# w2aew.net
KiCad netlist of a schematic drawn in EAGLE
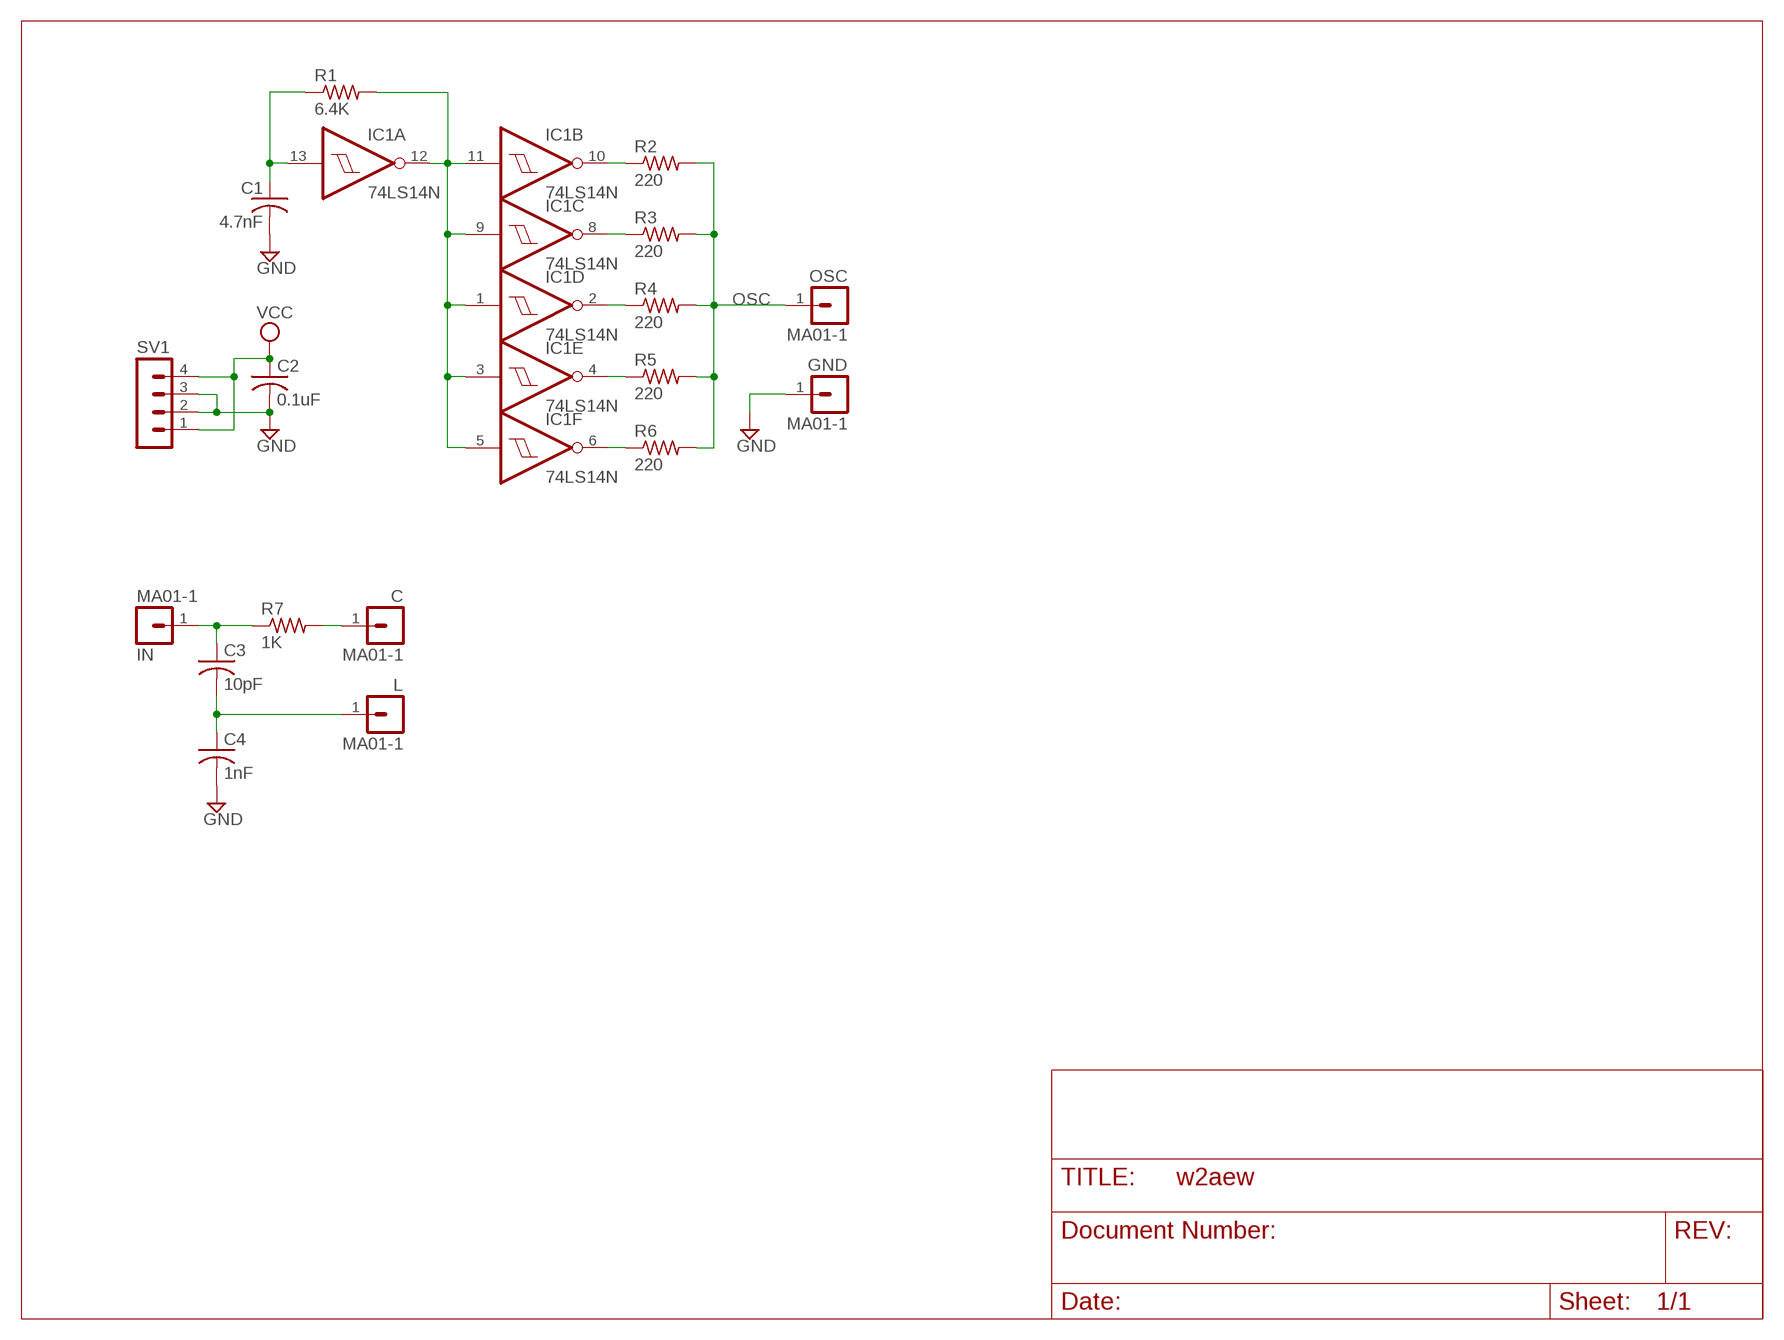
[diagram p0: schematic, sheet 1]

(export (version "E")
  (design (tool "Eeschema 10.0.6"))
  (components
    (comp (ref "C")
      (value "MA01-1")
      (footprint "eagle-import:MA01-1")
      (libsource (lib "eagle-import") (part "MA01-1"))
    )
    (comp (ref "C1")
      (value "4.7nF")
      (footprint "eagle-import:C050-025X075")
      (libsource (lib "eagle-import") (part "C-US050-025X075"))
    )
    (comp (ref "C2")
      (value "0.1uF")
      (footprint "eagle-import:C050-025X075")
      (libsource (lib "eagle-import") (part "C-US050-025X075"))
    )
    (comp (ref "C3")
      (value "10pF")
      (footprint "eagle-import:C050-025X075")
      (libsource (lib "eagle-import") (part "C-US050-025X075"))
    )
    (comp (ref "C4")
      (value "1nF")
      (footprint "eagle-import:C050-025X075")
      (libsource (lib "eagle-import") (part "C-US050-025X075"))
    )
    (comp (ref "GND")
      (value "MA01-1")
      (footprint "eagle-import:MA01-1")
      (libsource (lib "eagle-import") (part "MA01-1"))
    )
    (comp (ref "IC1")
      (value "74LS14N")
      (footprint "eagle-import:DIL14")
      (libsource (lib "eagle-import") (part "7414NLS"))
    )
    (comp (ref "IN")
      (value "MA01-1")
      (footprint "eagle-import:MA01-1")
      (libsource (lib "eagle-import") (part "MA01-1"))
    )
    (comp (ref "L")
      (value "MA01-1")
      (footprint "eagle-import:MA01-1")
      (libsource (lib "eagle-import") (part "MA01-1"))
    )
    (comp (ref "OSC")
      (value "MA01-1")
      (footprint "eagle-import:MA01-1")
      (libsource (lib "eagle-import") (part "MA01-1"))
    )
    (comp (ref "R1")
      (value "6.4K")
      (footprint "eagle-import:0207_10")
      (libsource (lib "eagle-import") (part "R-US_0207/10"))
    )
    (comp (ref "R2")
      (value "220")
      (footprint "eagle-import:0207_10")
      (libsource (lib "eagle-import") (part "R-US_0207/10"))
    )
    (comp (ref "R3")
      (value "220")
      (footprint "eagle-import:0207_10")
      (libsource (lib "eagle-import") (part "R-US_0207/10"))
    )
    (comp (ref "R4")
      (value "220")
      (footprint "eagle-import:0207_10")
      (libsource (lib "eagle-import") (part "R-US_0207/10"))
    )
    (comp (ref "R5")
      (value "220")
      (footprint "eagle-import:0207_10")
      (libsource (lib "eagle-import") (part "R-US_0207/10"))
    )
    (comp (ref "R6")
      (value "220")
      (footprint "eagle-import:0207_10")
      (libsource (lib "eagle-import") (part "R-US_0207/10"))
    )
    (comp (ref "R7")
      (value "1K")
      (footprint "eagle-import:0207_10")
      (libsource (lib "eagle-import") (part "R-US_0207/10"))
    )
    (comp (ref "SV1")
      (value "MA04-1")
      (footprint "eagle-import:MA04-1")
      (libsource (lib "eagle-import") (part "MA04-1"))
    )
  )
  (nets
    (net (code "1") (name "/OSC") (class "Default")
      (node (ref "OSC") (pin "1") (pinfunction "1_1") (pintype "passive"))
      (node (ref "R2") (pin "2") (pinfunction "2_2") (pintype "passive"))
      (node (ref "R3") (pin "2") (pinfunction "2_2") (pintype "passive"))
      (node (ref "R4") (pin "2") (pinfunction "2_2") (pintype "passive"))
      (node (ref "R5") (pin "2") (pinfunction "2_2") (pintype "passive"))
      (node (ref "R6") (pin "2") (pinfunction "2_2") (pintype "passive"))
    )
    (net (code "2") (name "GND") (class "Default")
      (node (ref "C1") (pin "2") (pinfunction "2_2") (pintype "passive"))
      (node (ref "C2") (pin "2") (pinfunction "2_2") (pintype "passive"))
      (node (ref "C4") (pin "2") (pinfunction "2_2") (pintype "passive"))
      (node (ref "GND") (pin "1") (pinfunction "1_1") (pintype "passive"))
      (node (ref "SV1") (pin "2") (pinfunction "2_2") (pintype "passive"))
      (node (ref "SV1") (pin "3") (pinfunction "3_3") (pintype "passive"))
    )
    (net (code "3") (name "Net-(C-Pad1)") (class "Default")
      (node (ref "C") (pin "1") (pinfunction "1_1") (pintype "passive"))
      (node (ref "R7") (pin "2") (pinfunction "2_2") (pintype "passive"))
    )
    (net (code "4") (name "Net-(C3-Pad1)") (class "Default")
      (node (ref "C3") (pin "1") (pinfunction "1_1") (pintype "passive"))
      (node (ref "IN") (pin "1") (pinfunction "1_1") (pintype "passive"))
      (node (ref "R7") (pin "1") (pinfunction "1_1") (pintype "passive"))
    )
    (net (code "5") (name "Net-(C3-Pad2)") (class "Default")
      (node (ref "C3") (pin "2") (pinfunction "2_2") (pintype "passive"))
      (node (ref "C4") (pin "1") (pinfunction "1_1") (pintype "passive"))
      (node (ref "L") (pin "1") (pinfunction "1_1") (pintype "passive"))
    )
    (net (code "6") (name "Net-(IC1A-I)") (class "Default")
      (node (ref "C1") (pin "1") (pinfunction "1_1") (pintype "passive"))
      (node (ref "IC1") (pin "13") (pinfunction "I_13") (pintype "input"))
      (node (ref "R1") (pin "1") (pinfunction "1_1") (pintype "passive"))
    )
    (net (code "7") (name "Net-(IC1A-O)") (class "Default")
      (node (ref "IC1") (pin "1") (pinfunction "I_1") (pintype "input"))
      (node (ref "IC1") (pin "11") (pinfunction "I_11") (pintype "input"))
      (node (ref "IC1") (pin "12") (pinfunction "O_12") (pintype "output"))
      (node (ref "IC1") (pin "3") (pinfunction "I_3") (pintype "input"))
      (node (ref "IC1") (pin "5") (pinfunction "I_5") (pintype "input"))
      (node (ref "IC1") (pin "9") (pinfunction "I_9") (pintype "input"))
      (node (ref "R1") (pin "2") (pinfunction "2_2") (pintype "passive"))
    )
    (net (code "8") (name "Net-(IC1B-O)") (class "Default")
      (node (ref "IC1") (pin "10") (pinfunction "O_10") (pintype "output"))
      (node (ref "R2") (pin "1") (pinfunction "1_1") (pintype "passive"))
    )
    (net (code "9") (name "Net-(IC1C-O)") (class "Default")
      (node (ref "IC1") (pin "8") (pinfunction "O_8") (pintype "output"))
      (node (ref "R3") (pin "1") (pinfunction "1_1") (pintype "passive"))
    )
    (net (code "10") (name "Net-(IC1D-O)") (class "Default")
      (node (ref "IC1") (pin "2") (pinfunction "O_2") (pintype "output"))
      (node (ref "R4") (pin "1") (pinfunction "1_1") (pintype "passive"))
    )
    (net (code "11") (name "Net-(IC1E-O)") (class "Default")
      (node (ref "IC1") (pin "4") (pinfunction "O_4") (pintype "output"))
      (node (ref "R5") (pin "1") (pinfunction "1_1") (pintype "passive"))
    )
    (net (code "12") (name "Net-(IC1F-O)") (class "Default")
      (node (ref "IC1") (pin "6") (pinfunction "O_6") (pintype "output"))
      (node (ref "R6") (pin "1") (pinfunction "1_1") (pintype "passive"))
    )
    (net (code "13") (name "VCC") (class "Default")
      (node (ref "C2") (pin "1") (pinfunction "1_1") (pintype "passive"))
      (node (ref "SV1") (pin "1") (pinfunction "1_1") (pintype "passive"))
      (node (ref "SV1") (pin "4") (pinfunction "4_4") (pintype "passive"))
    )
  )
)
